# Neutro.net
KiCad netlist of a schematic drawn in Altium Designer
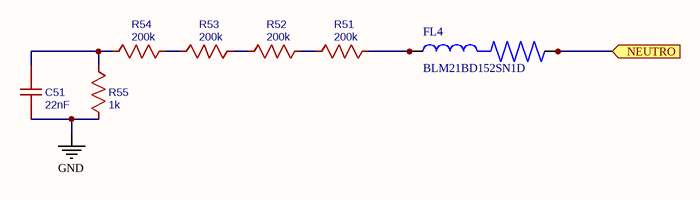
[diagram p0: Neutro.SchDoc]

(export (version "E")
  (design (tool "Eeschema 10.0.6"))
  (components
    (comp (ref "C51")
      (value "22nF")
      (footprint "GRM31C5C1E104GA01L:CAPC3216X190")
      (libsource (lib "altium-import") (part "root_0_22nF_"))
    )
    (comp (ref "FL4")
      (value "BLM21BD152SN1D")
      (footprint "BEADC2012X105N")
      (description "1.5 kOhms @ 100MHz 1 Signal Line Ferrite Bead 0805 (2012 Metric) 250mA 450mOhm")
      (fields (field (name "MF") "Murata"))
      (libsource (lib "BLM21BD152SN1D") (part "BLM21BD152SN1D"))
    )
    (comp (ref "R51")
      (value "200k")
      (footprint "SamacSys:RESC3216X75N")
      (libsource (lib "altium-import") (part "root_0_330k_"))
    )
    (comp (ref "R52")
      (value "200k")
      (footprint "SamacSys:RESC3216X75N")
      (libsource (lib "altium-import") (part "root_0_330k_"))
    )
    (comp (ref "R53")
      (value "200k")
      (footprint "SamacSys:RESC3216X75N")
      (libsource (lib "altium-import") (part "root_0_330k_"))
    )
    (comp (ref "R54")
      (value "200k")
      (footprint "SamacSys:RESC3216X75N")
      (libsource (lib "altium-import") (part "root_0_330k_"))
    )
    (comp (ref "R55")
      (value "1k")
      (footprint "SamacSys:RESC3216X75N")
      (libsource (lib "altium-import") (part "root_1_1k_"))
    )
  )
  (nets
    (net (code "1") (name "/NEUTRO") (class "Default")
      (node (ref "FL4") (pin "1") (pinfunction "1_1") (pintype "passive"))
    )
    (net (code "2") (name "GND") (class "Default")
      (node (ref "C51") (pin "1") (pinfunction "1_1") (pintype "passive"))
      (node (ref "R55") (pin "1") (pinfunction "1_1") (pintype "passive"))
    )
    (net (code "3") (name "Net-(C51-Pad2)") (class "Default")
      (node (ref "C51") (pin "2") (pinfunction "2_2") (pintype "passive"))
      (node (ref "R54") (pin "1") (pinfunction "1_1") (pintype "passive"))
      (node (ref "R55") (pin "2") (pinfunction "2_2") (pintype "passive"))
    )
    (net (code "4") (name "Net-(FL4-Pad2)") (class "Default")
      (node (ref "FL4") (pin "2") (pinfunction "2_2") (pintype "passive"))
      (node (ref "R51") (pin "2") (pinfunction "2_2") (pintype "passive"))
    )
    (net (code "5") (name "Net-(R51-Pad1)") (class "Default")
      (node (ref "R51") (pin "1") (pinfunction "1_1") (pintype "passive"))
      (node (ref "R52") (pin "2") (pinfunction "2_2") (pintype "passive"))
    )
    (net (code "6") (name "Net-(R52-Pad1)") (class "Default")
      (node (ref "R52") (pin "1") (pinfunction "1_1") (pintype "passive"))
      (node (ref "R53") (pin "2") (pinfunction "2_2") (pintype "passive"))
    )
    (net (code "7") (name "Net-(R53-Pad1)") (class "Default")
      (node (ref "R53") (pin "1") (pinfunction "1_1") (pintype "passive"))
      (node (ref "R54") (pin "2") (pinfunction "2_2") (pintype "passive"))
    )
  )
)
